# mac_se_power_switch.net
KiCad netlist of a schematic drawn in EAGLE
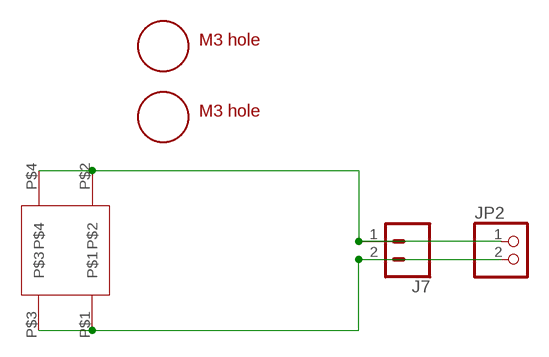
[diagram p0: schematic, sheet 1]

(export (version "E")
  (design (tool "Eeschema 10.0.6"))
  (components
    (comp (ref "J7")
      (value "CONN_023.5MM-NO_SILK")
      (footprint "eagle-import:SCREWTERMINAL-3.5MM-2-NS")
      (libsource (lib "eagle-import") (part "CONN_023.5MM-NO_SILK"))
    )
    (comp (ref "JP2")
      (value "PINHD-1X2/90")
      (footprint "eagle-import:1X02_90")
      (libsource (lib "eagle-import") (part "PINHD-1X2/90"))
    )
    (comp (ref "U$1")
      (value "ROCK_SW")
      (footprint "eagle-import:ROCK_SWITCH")
      (libsource (lib "eagle-import") (part "ROCK_SW"))
    )
    (comp (ref "U$2")
      (value "M3_MOUNTING_HOLE")
      (footprint "eagle-import:M3_MOUNTING_HOLE_PACK")
      (libsource (lib "eagle-import") (part "M3_MOUNTING_HOLE"))
    )
    (comp (ref "U$3")
      (value "M3_MOUNTING_HOLE")
      (footprint "eagle-import:M3_MOUNTING_HOLE_PACK")
      (libsource (lib "eagle-import") (part "M3_MOUNTING_HOLE"))
    )
  )
  (nets
    (net (code "1") (name "Net-(J7-Pad1)") (class "Default")
      (node (ref "J7") (pin "1") (pinfunction "1_1") (pintype "passive"))
      (node (ref "JP2") (pin "1") (pinfunction "1_1") (pintype "passive"))
      (node (ref "U$1") (pin "P$2") (pinfunction "P$2_P$2") (pintype "bidirectional"))
      (node (ref "U$1") (pin "P$4") (pinfunction "P$4_P$4") (pintype "bidirectional"))
    )
    (net (code "2") (name "Net-(J7-Pad2)") (class "Default")
      (node (ref "J7") (pin "2") (pinfunction "2_2") (pintype "passive"))
      (node (ref "JP2") (pin "2") (pinfunction "2_2") (pintype "passive"))
      (node (ref "U$1") (pin "P$1") (pinfunction "P$1_P$1") (pintype "bidirectional"))
      (node (ref "U$1") (pin "P$3") (pinfunction "P$3_P$3") (pintype "bidirectional"))
    )
  )
)
